# ArduinoMega.net
KiCad netlist of a schematic drawn in Altium Designer
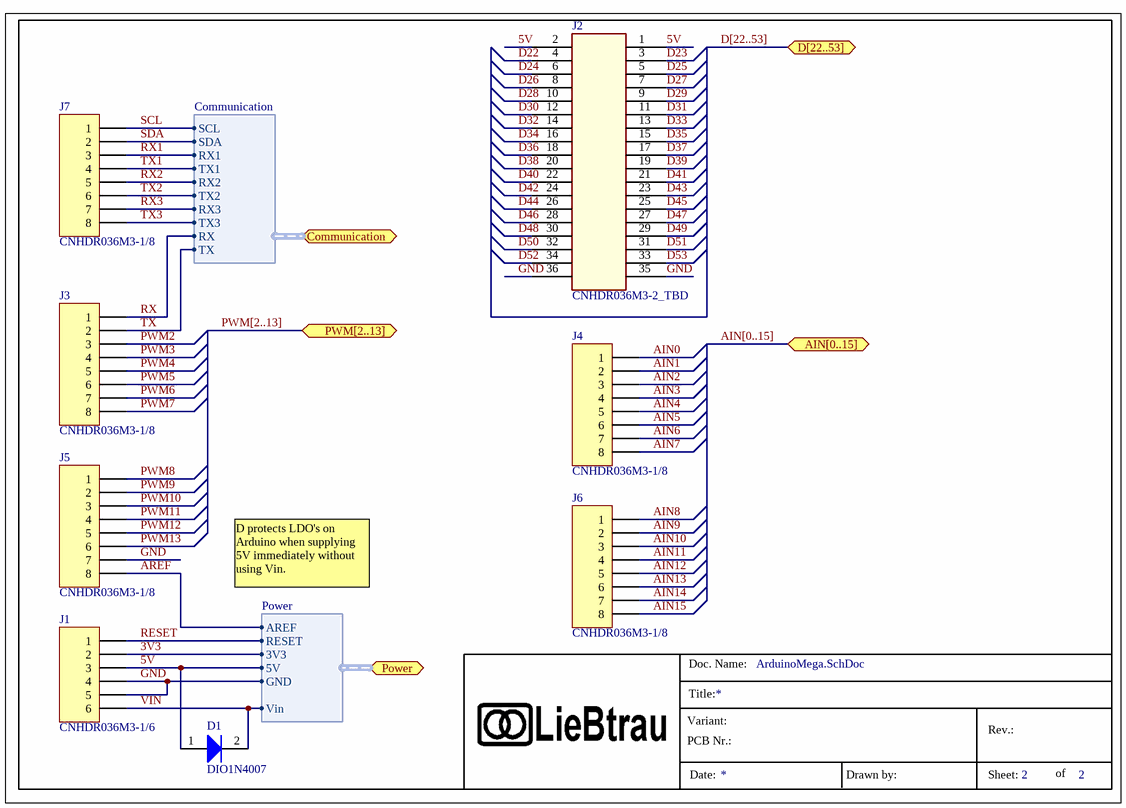
[diagram p0: ArduinoMega.SchDoc]

(export (version "E")
  (design (tool "Eeschema 10.0.6"))
  (components
    (comp (ref "D1")
      (value "DIO1N4007")
      (footprint "DO-41")
      (description "1 Amp General Purpose Rectifier")
      (libsource (lib "Testing") (part "D_DIODE"))
    )
    (comp (ref "J1")
      (value "CNHDR036M3-1/6")
      (footprint "J_HDR1X6")
      (libsource (lib "Testing") (part "J_6P"))
    )
    (comp (ref "J2")
      (value "CNHDR036M3-2_TBD")
      (footprint "J_HDR2X18")
      (libsource (lib "Testing") (part "J_2X18P"))
    )
    (comp (ref "J3")
      (value "CNHDR036M3-1/8")
      (footprint "J_HDR1X8")
      (libsource (lib "Testing") (part "J_8P"))
    )
    (comp (ref "J4")
      (value "CNHDR036M3-1/8")
      (footprint "J_HDR1X8")
      (libsource (lib "Testing") (part "J_8P"))
    )
    (comp (ref "J5")
      (value "CNHDR036M3-1/8")
      (footprint "J_HDR1X8")
      (libsource (lib "Testing") (part "J_8P"))
    )
    (comp (ref "J6")
      (value "CNHDR036M3-1/8")
      (footprint "J_HDR1X8")
      (libsource (lib "Testing") (part "J_8P"))
    )
    (comp (ref "J7")
      (value "CNHDR036M3-1/8")
      (footprint "J_HDR1X8")
      (libsource (lib "Testing") (part "J_8P"))
    )
  )
  (nets
    (net (code "3") (name "/3V3") (class "Default")
      (node (ref "J1") (pin "2") (pinfunction "2_2") (pintype "passive"))
    )
    (net (code "4") (name "/5V") (class "Default")
      (node (ref "D1") (pin "1") (pinfunction "A_1") (pintype "passive"))
      (node (ref "J1") (pin "3") (pinfunction "3_3") (pintype "passive"))
      (node (ref "J2") (pin "1") (pinfunction "1_1") (pintype "passive"))
      (node (ref "J2") (pin "2") (pinfunction "2_2") (pintype "passive"))
    )
    (net (code "5") (name "/AIN0") (class "Default")
      (node (ref "J4") (pin "1") (pinfunction "1_1") (pintype "passive"))
    )
    (net (code "6") (name "/AIN1") (class "Default")
      (node (ref "J4") (pin "2") (pinfunction "2_2") (pintype "passive"))
    )
    (net (code "7") (name "/AIN2") (class "Default")
      (node (ref "J4") (pin "3") (pinfunction "3_3") (pintype "passive"))
    )
    (net (code "8") (name "/AIN3") (class "Default")
      (node (ref "J4") (pin "4") (pinfunction "4_4") (pintype "passive"))
    )
    (net (code "9") (name "/AIN4") (class "Default")
      (node (ref "J4") (pin "5") (pinfunction "5_5") (pintype "passive"))
    )
    (net (code "10") (name "/AIN5") (class "Default")
      (node (ref "J4") (pin "6") (pinfunction "6_6") (pintype "passive"))
    )
    (net (code "11") (name "/AIN6") (class "Default")
      (node (ref "J4") (pin "7") (pinfunction "7_7") (pintype "passive"))
    )
    (net (code "12") (name "/AIN7") (class "Default")
      (node (ref "J4") (pin "8") (pinfunction "8_8") (pintype "passive"))
    )
    (net (code "13") (name "/AIN8") (class "Default")
      (node (ref "J6") (pin "1") (pinfunction "1_1") (pintype "passive"))
    )
    (net (code "14") (name "/AIN9") (class "Default")
      (node (ref "J6") (pin "2") (pinfunction "2_2") (pintype "passive"))
    )
    (net (code "15") (name "/AIN10") (class "Default")
      (node (ref "J6") (pin "3") (pinfunction "3_3") (pintype "passive"))
    )
    (net (code "16") (name "/AIN11") (class "Default")
      (node (ref "J6") (pin "4") (pinfunction "4_4") (pintype "passive"))
    )
    (net (code "17") (name "/AIN12") (class "Default")
      (node (ref "J6") (pin "5") (pinfunction "5_5") (pintype "passive"))
    )
    (net (code "18") (name "/AIN13") (class "Default")
      (node (ref "J6") (pin "6") (pinfunction "6_6") (pintype "passive"))
    )
    (net (code "19") (name "/AIN14") (class "Default")
      (node (ref "J6") (pin "7") (pinfunction "7_7") (pintype "passive"))
    )
    (net (code "20") (name "/AIN15") (class "Default")
      (node (ref "J6") (pin "8") (pinfunction "8_8") (pintype "passive"))
    )
    (net (code "22") (name "/AREF") (class "Default")
      (node (ref "J5") (pin "8") (pinfunction "8_8") (pintype "passive"))
    )
    (net (code "23") (name "/D22") (class "Default")
      (node (ref "J2") (pin "4") (pinfunction "4_4") (pintype "passive"))
    )
    (net (code "24") (name "/D23") (class "Default")
      (node (ref "J2") (pin "3") (pinfunction "3_3") (pintype "passive"))
    )
    (net (code "25") (name "/D24") (class "Default")
      (node (ref "J2") (pin "6") (pinfunction "6_6") (pintype "passive"))
    )
    (net (code "26") (name "/D25") (class "Default")
      (node (ref "J2") (pin "5") (pinfunction "5_5") (pintype "passive"))
    )
    (net (code "27") (name "/D26") (class "Default")
      (node (ref "J2") (pin "8") (pinfunction "8_8") (pintype "passive"))
    )
    (net (code "28") (name "/D27") (class "Default")
      (node (ref "J2") (pin "7") (pinfunction "7_7") (pintype "passive"))
    )
    (net (code "29") (name "/D28") (class "Default")
      (node (ref "J2") (pin "10") (pinfunction "10_10") (pintype "passive"))
    )
    (net (code "30") (name "/D29") (class "Default")
      (node (ref "J2") (pin "9") (pinfunction "9_9") (pintype "passive"))
    )
    (net (code "31") (name "/D30") (class "Default")
      (node (ref "J2") (pin "12") (pinfunction "12_12") (pintype "passive"))
    )
    (net (code "32") (name "/D31") (class "Default")
      (node (ref "J2") (pin "11") (pinfunction "11_11") (pintype "passive"))
    )
    (net (code "33") (name "/D32") (class "Default")
      (node (ref "J2") (pin "14") (pinfunction "14_14") (pintype "passive"))
    )
    (net (code "34") (name "/D33") (class "Default")
      (node (ref "J2") (pin "13") (pinfunction "13_13") (pintype "passive"))
    )
    (net (code "35") (name "/D34") (class "Default")
      (node (ref "J2") (pin "16") (pinfunction "16_16") (pintype "passive"))
    )
    (net (code "36") (name "/D35") (class "Default")
      (node (ref "J2") (pin "15") (pinfunction "15_15") (pintype "passive"))
    )
    (net (code "37") (name "/D36") (class "Default")
      (node (ref "J2") (pin "18") (pinfunction "18_18") (pintype "passive"))
    )
    (net (code "38") (name "/D37") (class "Default")
      (node (ref "J2") (pin "17") (pinfunction "17_17") (pintype "passive"))
    )
    (net (code "39") (name "/D38") (class "Default")
      (node (ref "J2") (pin "20") (pinfunction "20_20") (pintype "passive"))
    )
    (net (code "40") (name "/D39") (class "Default")
      (node (ref "J2") (pin "19") (pinfunction "19_19") (pintype "passive"))
    )
    (net (code "41") (name "/D40") (class "Default")
      (node (ref "J2") (pin "22") (pinfunction "22_22") (pintype "passive"))
    )
    (net (code "42") (name "/D41") (class "Default")
      (node (ref "J2") (pin "21") (pinfunction "21_21") (pintype "passive"))
    )
    (net (code "43") (name "/D42") (class "Default")
      (node (ref "J2") (pin "24") (pinfunction "24_24") (pintype "passive"))
    )
    (net (code "44") (name "/D43") (class "Default")
      (node (ref "J2") (pin "23") (pinfunction "23_23") (pintype "passive"))
    )
    (net (code "45") (name "/D44") (class "Default")
      (node (ref "J2") (pin "26") (pinfunction "26_26") (pintype "passive"))
    )
    (net (code "46") (name "/D45") (class "Default")
      (node (ref "J2") (pin "25") (pinfunction "25_25") (pintype "passive"))
    )
    (net (code "47") (name "/D46") (class "Default")
      (node (ref "J2") (pin "28") (pinfunction "28_28") (pintype "passive"))
    )
    (net (code "48") (name "/D47") (class "Default")
      (node (ref "J2") (pin "27") (pinfunction "27_27") (pintype "passive"))
    )
    (net (code "49") (name "/D48") (class "Default")
      (node (ref "J2") (pin "30") (pinfunction "30_30") (pintype "passive"))
    )
    (net (code "50") (name "/D49") (class "Default")
      (node (ref "J2") (pin "29") (pinfunction "29_29") (pintype "passive"))
    )
    (net (code "51") (name "/D50") (class "Default")
      (node (ref "J2") (pin "32") (pinfunction "32_32") (pintype "passive"))
    )
    (net (code "52") (name "/D51") (class "Default")
      (node (ref "J2") (pin "31") (pinfunction "31_31") (pintype "passive"))
    )
    (net (code "53") (name "/D52") (class "Default")
      (node (ref "J2") (pin "34") (pinfunction "34_34") (pintype "passive"))
    )
    (net (code "54") (name "/D53") (class "Default")
      (node (ref "J2") (pin "33") (pinfunction "33_33") (pintype "passive"))
    )
    (net (code "56") (name "/GND") (class "Default")
      (node (ref "J1") (pin "4") (pinfunction "4_4") (pintype "passive"))
      (node (ref "J1") (pin "5") (pinfunction "5_5") (pintype "passive"))
      (node (ref "J2") (pin "35") (pinfunction "35_35") (pintype "passive"))
      (node (ref "J2") (pin "36") (pinfunction "36_36") (pintype "passive"))
      (node (ref "J5") (pin "7") (pinfunction "7_7") (pintype "passive"))
    )
    (net (code "57") (name "/PWM2") (class "Default")
      (node (ref "J3") (pin "3") (pinfunction "3_3") (pintype "passive"))
    )
    (net (code "58") (name "/PWM3") (class "Default")
      (node (ref "J3") (pin "4") (pinfunction "4_4") (pintype "passive"))
    )
    (net (code "59") (name "/PWM4") (class "Default")
      (node (ref "J3") (pin "5") (pinfunction "5_5") (pintype "passive"))
    )
    (net (code "60") (name "/PWM5") (class "Default")
      (node (ref "J3") (pin "6") (pinfunction "6_6") (pintype "passive"))
    )
    (net (code "61") (name "/PWM6") (class "Default")
      (node (ref "J3") (pin "7") (pinfunction "7_7") (pintype "passive"))
    )
    (net (code "62") (name "/PWM7") (class "Default")
      (node (ref "J3") (pin "8") (pinfunction "8_8") (pintype "passive"))
    )
    (net (code "63") (name "/PWM8") (class "Default")
      (node (ref "J5") (pin "1") (pinfunction "1_1") (pintype "passive"))
    )
    (net (code "64") (name "/PWM9") (class "Default")
      (node (ref "J5") (pin "2") (pinfunction "2_2") (pintype "passive"))
    )
    (net (code "65") (name "/PWM10") (class "Default")
      (node (ref "J5") (pin "3") (pinfunction "3_3") (pintype "passive"))
    )
    (net (code "66") (name "/PWM11") (class "Default")
      (node (ref "J5") (pin "4") (pinfunction "4_4") (pintype "passive"))
    )
    (net (code "67") (name "/PWM12") (class "Default")
      (node (ref "J5") (pin "5") (pinfunction "5_5") (pintype "passive"))
    )
    (net (code "68") (name "/PWM13") (class "Default")
      (node (ref "J5") (pin "6") (pinfunction "6_6") (pintype "passive"))
    )
    (net (code "70") (name "/RESET") (class "Default")
      (node (ref "J1") (pin "1") (pinfunction "1_1") (pintype "passive"))
    )
    (net (code "71") (name "/RX") (class "Default")
      (node (ref "J3") (pin "1") (pinfunction "1_1") (pintype "passive"))
    )
    (net (code "72") (name "/RX1") (class "Default")
      (node (ref "J7") (pin "3") (pinfunction "3_3") (pintype "passive"))
    )
    (net (code "73") (name "/RX2") (class "Default")
      (node (ref "J7") (pin "5") (pinfunction "5_5") (pintype "passive"))
    )
    (net (code "74") (name "/RX3") (class "Default")
      (node (ref "J7") (pin "7") (pinfunction "7_7") (pintype "passive"))
    )
    (net (code "75") (name "/SCL") (class "Default")
      (node (ref "J7") (pin "1") (pinfunction "1_1") (pintype "passive"))
    )
    (net (code "76") (name "/SDA") (class "Default")
      (node (ref "J7") (pin "2") (pinfunction "2_2") (pintype "passive"))
    )
    (net (code "77") (name "/TX") (class "Default")
      (node (ref "J3") (pin "2") (pinfunction "2_2") (pintype "passive"))
    )
    (net (code "78") (name "/TX1") (class "Default")
      (node (ref "J7") (pin "4") (pinfunction "4_4") (pintype "passive"))
    )
    (net (code "79") (name "/TX2") (class "Default")
      (node (ref "J7") (pin "6") (pinfunction "6_6") (pintype "passive"))
    )
    (net (code "80") (name "/TX3") (class "Default")
      (node (ref "J7") (pin "8") (pinfunction "8_8") (pintype "passive"))
    )
    (net (code "81") (name "/VIN") (class "Default")
      (node (ref "D1") (pin "2") (pinfunction "K_2") (pintype "passive"))
      (node (ref "J1") (pin "6") (pinfunction "6_6") (pintype "passive"))
    )
  )
)
